# 24x16_RGB_Top.net
KiCad netlist of a schematic drawn in EAGLE
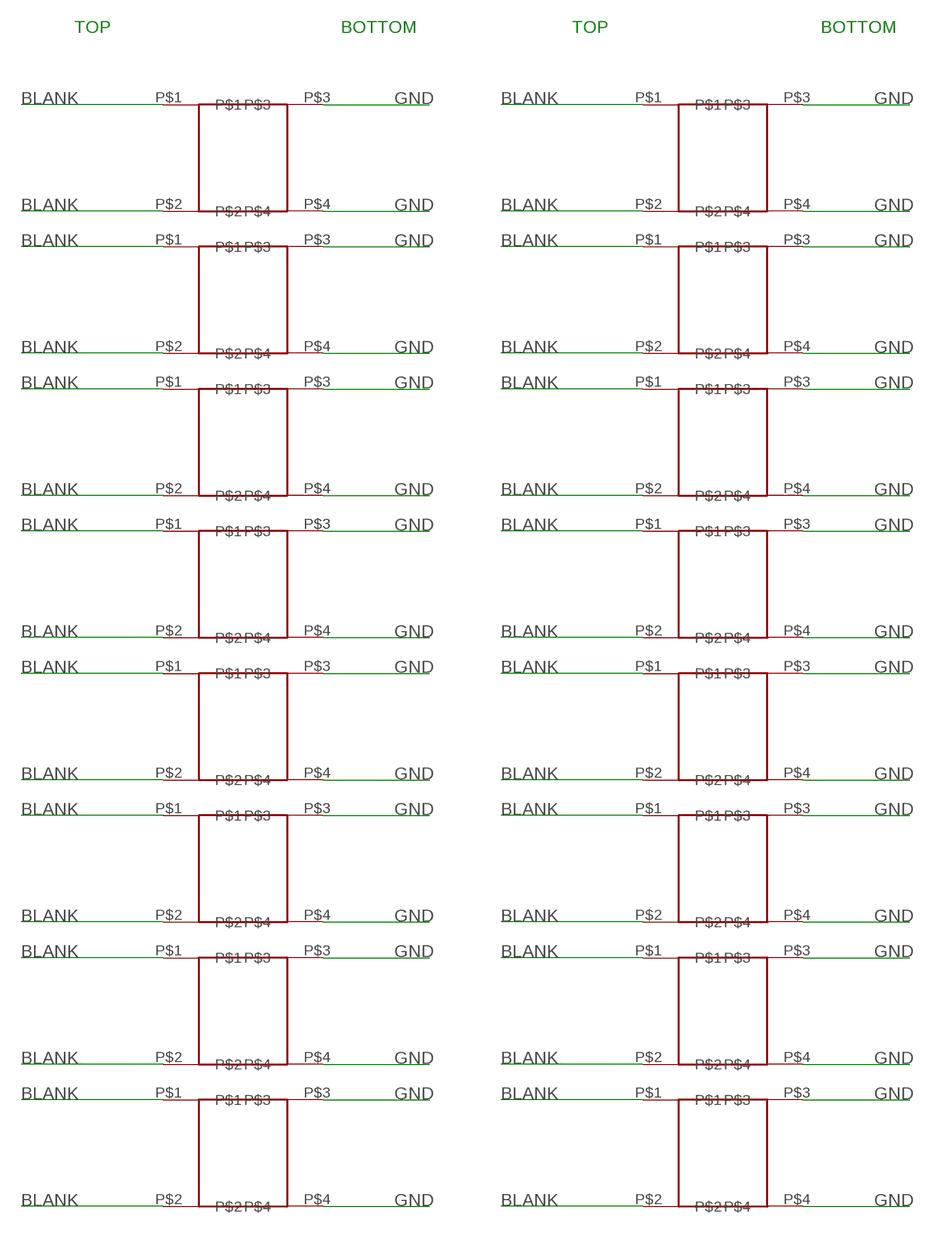
[diagram p0: schematic, sheet 1]
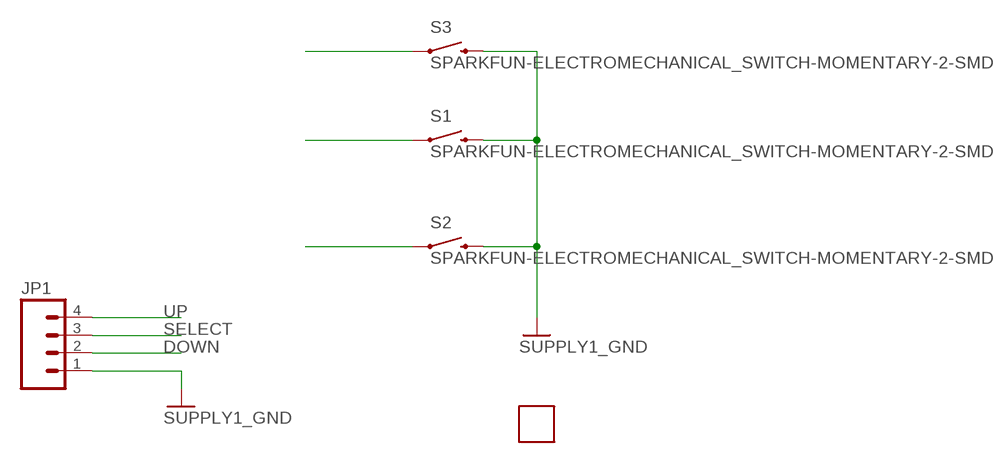
[diagram p1: schematic, sheet 2]

(export (version "E")
  (design (tool "Eeschema 10.0.6"))
  (components
    (comp (ref "SLOT1")
      (value "SLOT")
      (footprint "eagle-import:SLOT")
      (libsource (lib "eagle-import") (part "SLOT"))
    )
    (comp (ref "SLOT2")
      (value "SLOT")
      (footprint "eagle-import:SLOT")
      (libsource (lib "eagle-import") (part "SLOT"))
    )
    (comp (ref "SLOT3")
      (value "SLOT")
      (footprint "eagle-import:SLOT")
      (libsource (lib "eagle-import") (part "SLOT"))
    )
    (comp (ref "SLOT4")
      (value "SLOT")
      (footprint "eagle-import:SLOT")
      (libsource (lib "eagle-import") (part "SLOT"))
    )
    (comp (ref "SLOT5")
      (value "SLOT")
      (footprint "eagle-import:SLOT")
      (libsource (lib "eagle-import") (part "SLOT"))
    )
    (comp (ref "SLOT6")
      (value "SLOT")
      (footprint "eagle-import:SLOT")
      (libsource (lib "eagle-import") (part "SLOT"))
    )
    (comp (ref "SLOT7")
      (value "SLOT")
      (footprint "eagle-import:SLOT")
      (libsource (lib "eagle-import") (part "SLOT"))
    )
    (comp (ref "SLOT8")
      (value "SLOT")
      (footprint "eagle-import:SLOT")
      (libsource (lib "eagle-import") (part "SLOT"))
    )
    (comp (ref "SLOT9")
      (value "SLOT")
      (footprint "eagle-import:SLOT")
      (libsource (lib "eagle-import") (part "SLOT"))
    )
    (comp (ref "SLOT10")
      (value "SLOT")
      (footprint "eagle-import:SLOT")
      (libsource (lib "eagle-import") (part "SLOT"))
    )
    (comp (ref "SLOT11")
      (value "SLOT")
      (footprint "eagle-import:SLOT")
      (libsource (lib "eagle-import") (part "SLOT"))
    )
    (comp (ref "SLOT12")
      (value "SLOT")
      (footprint "eagle-import:SLOT")
      (libsource (lib "eagle-import") (part "SLOT"))
    )
    (comp (ref "SLOT13")
      (value "SLOT")
      (footprint "eagle-import:SLOT")
      (libsource (lib "eagle-import") (part "SLOT"))
    )
    (comp (ref "SLOT14")
      (value "SLOT")
      (footprint "eagle-import:SLOT")
      (libsource (lib "eagle-import") (part "SLOT"))
    )
    (comp (ref "SLOT15")
      (value "SLOT")
      (footprint "eagle-import:SLOT")
      (libsource (lib "eagle-import") (part "SLOT"))
    )
    (comp (ref "SLOT16")
      (value "SLOT")
      (footprint "eagle-import:SLOT")
      (libsource (lib "eagle-import") (part "SLOT"))
    )
    (comp (ref "JP1")
      (value "M04PTH")
      (footprint "eagle-import:1X04")
      (libsource (lib "eagle-import") (part "M04PTH"))
    )
    (comp (ref "S1")
      (value "SPARKFUN-ELECTROMECHANICAL_SWITCH-MOMENTARY-2-SMD-1101NE")
      (footprint "eagle-import:SPARKFUN-ELECTROMECHANICAL_TACTILE-SWITCH-1101NE")
      (libsource (lib "eagle-import") (part "SPARKFUN-ELECTROMECHANICAL_SWITCH-MOMENTARY-2-SMD-1101NE"))
    )
    (comp (ref "S2")
      (value "SPARKFUN-ELECTROMECHANICAL_SWITCH-MOMENTARY-2-SMD-1101NE")
      (footprint "eagle-import:SPARKFUN-ELECTROMECHANICAL_TACTILE-SWITCH-1101NE")
      (libsource (lib "eagle-import") (part "SPARKFUN-ELECTROMECHANICAL_SWITCH-MOMENTARY-2-SMD-1101NE"))
    )
    (comp (ref "S3")
      (value "SPARKFUN-ELECTROMECHANICAL_SWITCH-MOMENTARY-2-SMD-1101NE")
      (footprint "eagle-import:SPARKFUN-ELECTROMECHANICAL_TACTILE-SWITCH-1101NE")
      (libsource (lib "eagle-import") (part "SPARKFUN-ELECTROMECHANICAL_SWITCH-MOMENTARY-2-SMD-1101NE"))
    )
    (comp (ref "U$1")
      (value "USB_PANNEL")
      (footprint "eagle-import:USB_PANNEL")
      (libsource (lib "eagle-import") (part "USB_PANNEL"))
    )
  )
  (nets
    (net (code "1") (name "BLANK") (class "Default")
      (node (ref "SLOT1") (pin "P$1") (pinfunction "P$1_P$1") (pintype "bidirectional"))
      (node (ref "SLOT1") (pin "P$2") (pinfunction "P$2_P$2") (pintype "bidirectional"))
      (node (ref "SLOT10") (pin "P$1") (pinfunction "P$1_P$1") (pintype "bidirectional"))
      (node (ref "SLOT10") (pin "P$2") (pinfunction "P$2_P$2") (pintype "bidirectional"))
      (node (ref "SLOT11") (pin "P$1") (pinfunction "P$1_P$1") (pintype "bidirectional"))
      (node (ref "SLOT11") (pin "P$2") (pinfunction "P$2_P$2") (pintype "bidirectional"))
      (node (ref "SLOT12") (pin "P$1") (pinfunction "P$1_P$1") (pintype "bidirectional"))
      (node (ref "SLOT12") (pin "P$2") (pinfunction "P$2_P$2") (pintype "bidirectional"))
      (node (ref "SLOT13") (pin "P$1") (pinfunction "P$1_P$1") (pintype "bidirectional"))
      (node (ref "SLOT13") (pin "P$2") (pinfunction "P$2_P$2") (pintype "bidirectional"))
      (node (ref "SLOT14") (pin "P$1") (pinfunction "P$1_P$1") (pintype "bidirectional"))
      (node (ref "SLOT14") (pin "P$2") (pinfunction "P$2_P$2") (pintype "bidirectional"))
      (node (ref "SLOT15") (pin "P$1") (pinfunction "P$1_P$1") (pintype "bidirectional"))
      (node (ref "SLOT15") (pin "P$2") (pinfunction "P$2_P$2") (pintype "bidirectional"))
      (node (ref "SLOT16") (pin "P$1") (pinfunction "P$1_P$1") (pintype "bidirectional"))
      (node (ref "SLOT16") (pin "P$2") (pinfunction "P$2_P$2") (pintype "bidirectional"))
      (node (ref "SLOT2") (pin "P$1") (pinfunction "P$1_P$1") (pintype "bidirectional"))
      (node (ref "SLOT2") (pin "P$2") (pinfunction "P$2_P$2") (pintype "bidirectional"))
      (node (ref "SLOT3") (pin "P$1") (pinfunction "P$1_P$1") (pintype "bidirectional"))
      (node (ref "SLOT3") (pin "P$2") (pinfunction "P$2_P$2") (pintype "bidirectional"))
      (node (ref "SLOT4") (pin "P$1") (pinfunction "P$1_P$1") (pintype "bidirectional"))
      (node (ref "SLOT4") (pin "P$2") (pinfunction "P$2_P$2") (pintype "bidirectional"))
      (node (ref "SLOT5") (pin "P$1") (pinfunction "P$1_P$1") (pintype "bidirectional"))
      (node (ref "SLOT5") (pin "P$2") (pinfunction "P$2_P$2") (pintype "bidirectional"))
      (node (ref "SLOT6") (pin "P$1") (pinfunction "P$1_P$1") (pintype "bidirectional"))
      (node (ref "SLOT6") (pin "P$2") (pinfunction "P$2_P$2") (pintype "bidirectional"))
      (node (ref "SLOT7") (pin "P$1") (pinfunction "P$1_P$1") (pintype "bidirectional"))
      (node (ref "SLOT7") (pin "P$2") (pinfunction "P$2_P$2") (pintype "bidirectional"))
      (node (ref "SLOT8") (pin "P$1") (pinfunction "P$1_P$1") (pintype "bidirectional"))
      (node (ref "SLOT8") (pin "P$2") (pinfunction "P$2_P$2") (pintype "bidirectional"))
      (node (ref "SLOT9") (pin "P$1") (pinfunction "P$1_P$1") (pintype "bidirectional"))
      (node (ref "SLOT9") (pin "P$2") (pinfunction "P$2_P$2") (pintype "bidirectional"))
    )
    (net (code "2") (name "DOWN") (class "Default")
      (node (ref "JP1") (pin "2") (pinfunction "2_2") (pintype "passive"))
      (node (ref "S2") (pin "P$1") (pinfunction "1_P$1") (pintype "passive"))
    )
    (net (code "3") (name "GND") (class "Default")
      (node (ref "JP1") (pin "1") (pinfunction "1_1") (pintype "passive"))
      (node (ref "S1") (pin "P$2") (pinfunction "2_P$2") (pintype "passive"))
      (node (ref "S2") (pin "P$2") (pinfunction "2_P$2") (pintype "passive"))
      (node (ref "S3") (pin "P$2") (pinfunction "2_P$2") (pintype "passive"))
      (node (ref "SLOT1") (pin "P$3") (pinfunction "P$3_P$3") (pintype "bidirectional"))
      (node (ref "SLOT1") (pin "P$4") (pinfunction "P$4_P$4") (pintype "bidirectional"))
      (node (ref "SLOT10") (pin "P$3") (pinfunction "P$3_P$3") (pintype "bidirectional"))
      (node (ref "SLOT10") (pin "P$4") (pinfunction "P$4_P$4") (pintype "bidirectional"))
      (node (ref "SLOT11") (pin "P$3") (pinfunction "P$3_P$3") (pintype "bidirectional"))
      (node (ref "SLOT11") (pin "P$4") (pinfunction "P$4_P$4") (pintype "bidirectional"))
      (node (ref "SLOT12") (pin "P$3") (pinfunction "P$3_P$3") (pintype "bidirectional"))
      (node (ref "SLOT12") (pin "P$4") (pinfunction "P$4_P$4") (pintype "bidirectional"))
      (node (ref "SLOT13") (pin "P$3") (pinfunction "P$3_P$3") (pintype "bidirectional"))
      (node (ref "SLOT13") (pin "P$4") (pinfunction "P$4_P$4") (pintype "bidirectional"))
      (node (ref "SLOT14") (pin "P$3") (pinfunction "P$3_P$3") (pintype "bidirectional"))
      (node (ref "SLOT14") (pin "P$4") (pinfunction "P$4_P$4") (pintype "bidirectional"))
      (node (ref "SLOT15") (pin "P$3") (pinfunction "P$3_P$3") (pintype "bidirectional"))
      (node (ref "SLOT15") (pin "P$4") (pinfunction "P$4_P$4") (pintype "bidirectional"))
      (node (ref "SLOT16") (pin "P$3") (pinfunction "P$3_P$3") (pintype "bidirectional"))
      (node (ref "SLOT16") (pin "P$4") (pinfunction "P$4_P$4") (pintype "bidirectional"))
      (node (ref "SLOT2") (pin "P$3") (pinfunction "P$3_P$3") (pintype "bidirectional"))
      (node (ref "SLOT2") (pin "P$4") (pinfunction "P$4_P$4") (pintype "bidirectional"))
      (node (ref "SLOT3") (pin "P$3") (pinfunction "P$3_P$3") (pintype "bidirectional"))
      (node (ref "SLOT3") (pin "P$4") (pinfunction "P$4_P$4") (pintype "bidirectional"))
      (node (ref "SLOT4") (pin "P$3") (pinfunction "P$3_P$3") (pintype "bidirectional"))
      (node (ref "SLOT4") (pin "P$4") (pinfunction "P$4_P$4") (pintype "bidirectional"))
      (node (ref "SLOT5") (pin "P$3") (pinfunction "P$3_P$3") (pintype "bidirectional"))
      (node (ref "SLOT5") (pin "P$4") (pinfunction "P$4_P$4") (pintype "bidirectional"))
      (node (ref "SLOT6") (pin "P$3") (pinfunction "P$3_P$3") (pintype "bidirectional"))
      (node (ref "SLOT6") (pin "P$4") (pinfunction "P$4_P$4") (pintype "bidirectional"))
      (node (ref "SLOT7") (pin "P$3") (pinfunction "P$3_P$3") (pintype "bidirectional"))
      (node (ref "SLOT7") (pin "P$4") (pinfunction "P$4_P$4") (pintype "bidirectional"))
      (node (ref "SLOT8") (pin "P$3") (pinfunction "P$3_P$3") (pintype "bidirectional"))
      (node (ref "SLOT8") (pin "P$4") (pinfunction "P$4_P$4") (pintype "bidirectional"))
      (node (ref "SLOT9") (pin "P$3") (pinfunction "P$3_P$3") (pintype "bidirectional"))
      (node (ref "SLOT9") (pin "P$4") (pinfunction "P$4_P$4") (pintype "bidirectional"))
    )
    (net (code "4") (name "SELECT") (class "Default")
      (node (ref "JP1") (pin "3") (pinfunction "3_3") (pintype "passive"))
      (node (ref "S1") (pin "P$1") (pinfunction "1_P$1") (pintype "passive"))
    )
    (net (code "5") (name "UP") (class "Default")
      (node (ref "JP1") (pin "4") (pinfunction "4_4") (pintype "passive"))
      (node (ref "S3") (pin "P$1") (pinfunction "1_P$1") (pintype "passive"))
    )
  )
)
